# Super-Regenerative-FM-Tuner-ForcedQuench.net
KiCad netlist of a schematic drawn in EAGLE
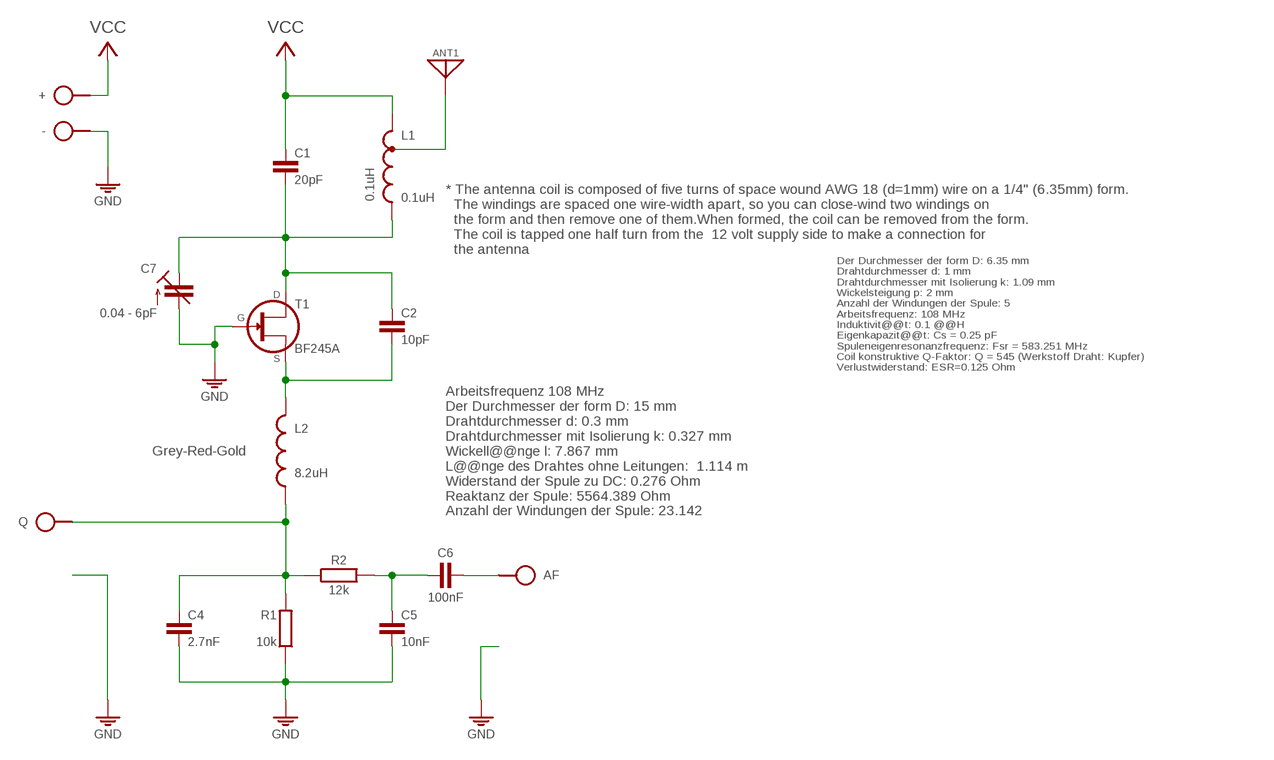
[diagram p0: schematic, sheet 1]

(export (version "E")
  (design (tool "Eeschema 10.0.6"))
  (components
    (comp (ref "+")
      (value "SPAD")
      (footprint "eagle-import:SPAD")
      (libsource (lib "eagle-import") (part "SPAD"))
    )
    (comp (ref "-")
      (value "SPAD")
      (footprint "eagle-import:SPAD")
      (libsource (lib "eagle-import") (part "SPAD"))
    )
    (comp (ref "AF")
      (value "SPAD")
      (footprint "eagle-import:SPAD")
      (libsource (lib "eagle-import") (part "SPAD"))
    )
    (comp (ref "ANT1")
      (value "ANT")
      (footprint "eagle-import:SPAD")
      (libsource (lib "eagle-import") (part "ANT"))
    )
    (comp (ref "C1")
      (value "20pF")
      (footprint "eagle-import:C025-015X024")
      (libsource (lib "eagle-import") (part "C025-015X024"))
    )
    (comp (ref "C2")
      (value "10pF")
      (footprint "eagle-import:C025-015X024")
      (libsource (lib "eagle-import") (part "C025-015X024"))
    )
    (comp (ref "C4")
      (value "2.7nF")
      (footprint "eagle-import:C050-020X044")
      (libsource (lib "eagle-import") (part "C050-020X044"))
    )
    (comp (ref "C5")
      (value "10nF")
      (footprint "eagle-import:C025-015X024")
      (libsource (lib "eagle-import") (part "C025-015X024"))
    )
    (comp (ref "C6")
      (value "100nF")
      (footprint "eagle-import:C050-020X044")
      (libsource (lib "eagle-import") (part "C-H050-020X044"))
    )
    (comp (ref "C7")
      (value "0.04 - 6pF")
      (footprint "eagle-import:CTRIMTZ03")
      (libsource (lib "eagle-import") (part "C-TR-PH20127-TZ03"))
    )
    (comp (ref "L1")
      (value "0.1uH")
      (footprint "eagle-import:L-08-7_8-TAP1")
      (libsource (lib "eagle-import") (part "L-TAP1L-08-7/5H"))
    )
    (comp (ref "L2")
      (value "8.2uH")
      (footprint "eagle-import:L-04_7-V")
      (libsource (lib "eagle-import") (part "L04/7-V"))
    )
    (comp (ref "Q")
      (value "SPAD")
      (footprint "eagle-import:SPAD")
      (libsource (lib "eagle-import") (part "SPAD"))
    )
    (comp (ref "R1")
      (value "10k")
      (footprint "eagle-import:0204_7")
      (libsource (lib "eagle-import") (part "R0204/7"))
    )
    (comp (ref "R2")
      (value "12k")
      (footprint "eagle-import:0204_7")
      (libsource (lib "eagle-import") (part "R-H0204/7"))
    )
    (comp (ref "T1")
      (value "BF245A")
      (footprint "eagle-import:TO92-GSD")
      (libsource (lib "eagle-import") (part "BF245BTO92"))
    )
  )
  (nets
    (net (code "1") (name "GND") (class "Default")
      (node (ref "-") (pin "1") (pinfunction "P$1_1") (pintype "passive"))
      (node (ref "C4") (pin "2") (pinfunction "2_2") (pintype "passive"))
      (node (ref "C5") (pin "2") (pinfunction "2_2") (pintype "passive"))
      (node (ref "C7") (pin "1") (pinfunction "A_1") (pintype "passive"))
      (node (ref "R1") (pin "1") (pinfunction "2_1") (pintype "passive"))
      (node (ref "T1") (pin "1") (pinfunction "G_1") (pintype "passive"))
    )
    (net (code "2") (name "Net-(AF-P$1)") (class "Default")
      (node (ref "AF") (pin "1") (pinfunction "P$1_1") (pintype "passive"))
      (node (ref "C6") (pin "2") (pinfunction "2_2") (pintype "passive"))
    )
    (net (code "3") (name "Net-(C5-Pad1)") (class "Default")
      (node (ref "C5") (pin "1") (pinfunction "1_1") (pintype "passive"))
      (node (ref "C6") (pin "1") (pinfunction "1_1") (pintype "passive"))
      (node (ref "R2") (pin "2") (pinfunction "2_2") (pintype "passive"))
    )
    (net (code "4") (name "Net-(C7-E)") (class "Default")
      (node (ref "C1") (pin "2") (pinfunction "2_2") (pintype "passive"))
      (node (ref "C2") (pin "1") (pinfunction "1_1") (pintype "passive"))
      (node (ref "C7") (pin "2") (pinfunction "E_2") (pintype "passive"))
      (node (ref "L1") (pin "2") (pinfunction "2_2") (pintype "passive"))
      (node (ref "T1") (pin "3") (pinfunction "D_3") (pintype "passive"))
    )
    (net (code "5") (name "Net-(L1-T)") (class "Default")
      (node (ref "ANT1") (pin "1") (pinfunction "1_1") (pintype "output"))
      (node (ref "L1") (pin "3") (pinfunction "T_3") (pintype "passive"))
    )
    (net (code "6") (name "Net-(Q-P$1)") (class "Default")
      (node (ref "C4") (pin "1") (pinfunction "1_1") (pintype "passive"))
      (node (ref "L2") (pin "2") (pinfunction "2_2") (pintype "passive"))
      (node (ref "Q") (pin "1") (pinfunction "P$1_1") (pintype "passive"))
      (node (ref "R1") (pin "2") (pinfunction "1_2") (pintype "passive"))
      (node (ref "R2") (pin "1") (pinfunction "1_1") (pintype "passive"))
    )
    (net (code "7") (name "Net-(T1-S)") (class "Default")
      (node (ref "C2") (pin "2") (pinfunction "2_2") (pintype "passive"))
      (node (ref "L2") (pin "1") (pinfunction "1_1") (pintype "passive"))
      (node (ref "T1") (pin "2") (pinfunction "S_2") (pintype "passive"))
    )
    (net (code "8") (name "VCC") (class "Default")
      (node (ref "+") (pin "1") (pinfunction "P$1_1") (pintype "passive"))
      (node (ref "C1") (pin "1") (pinfunction "1_1") (pintype "passive"))
      (node (ref "L1") (pin "1") (pinfunction "1_1") (pintype "passive"))
    )
  )
)
